# power.net
KiCad netlist of a schematic drawn in EAGLE
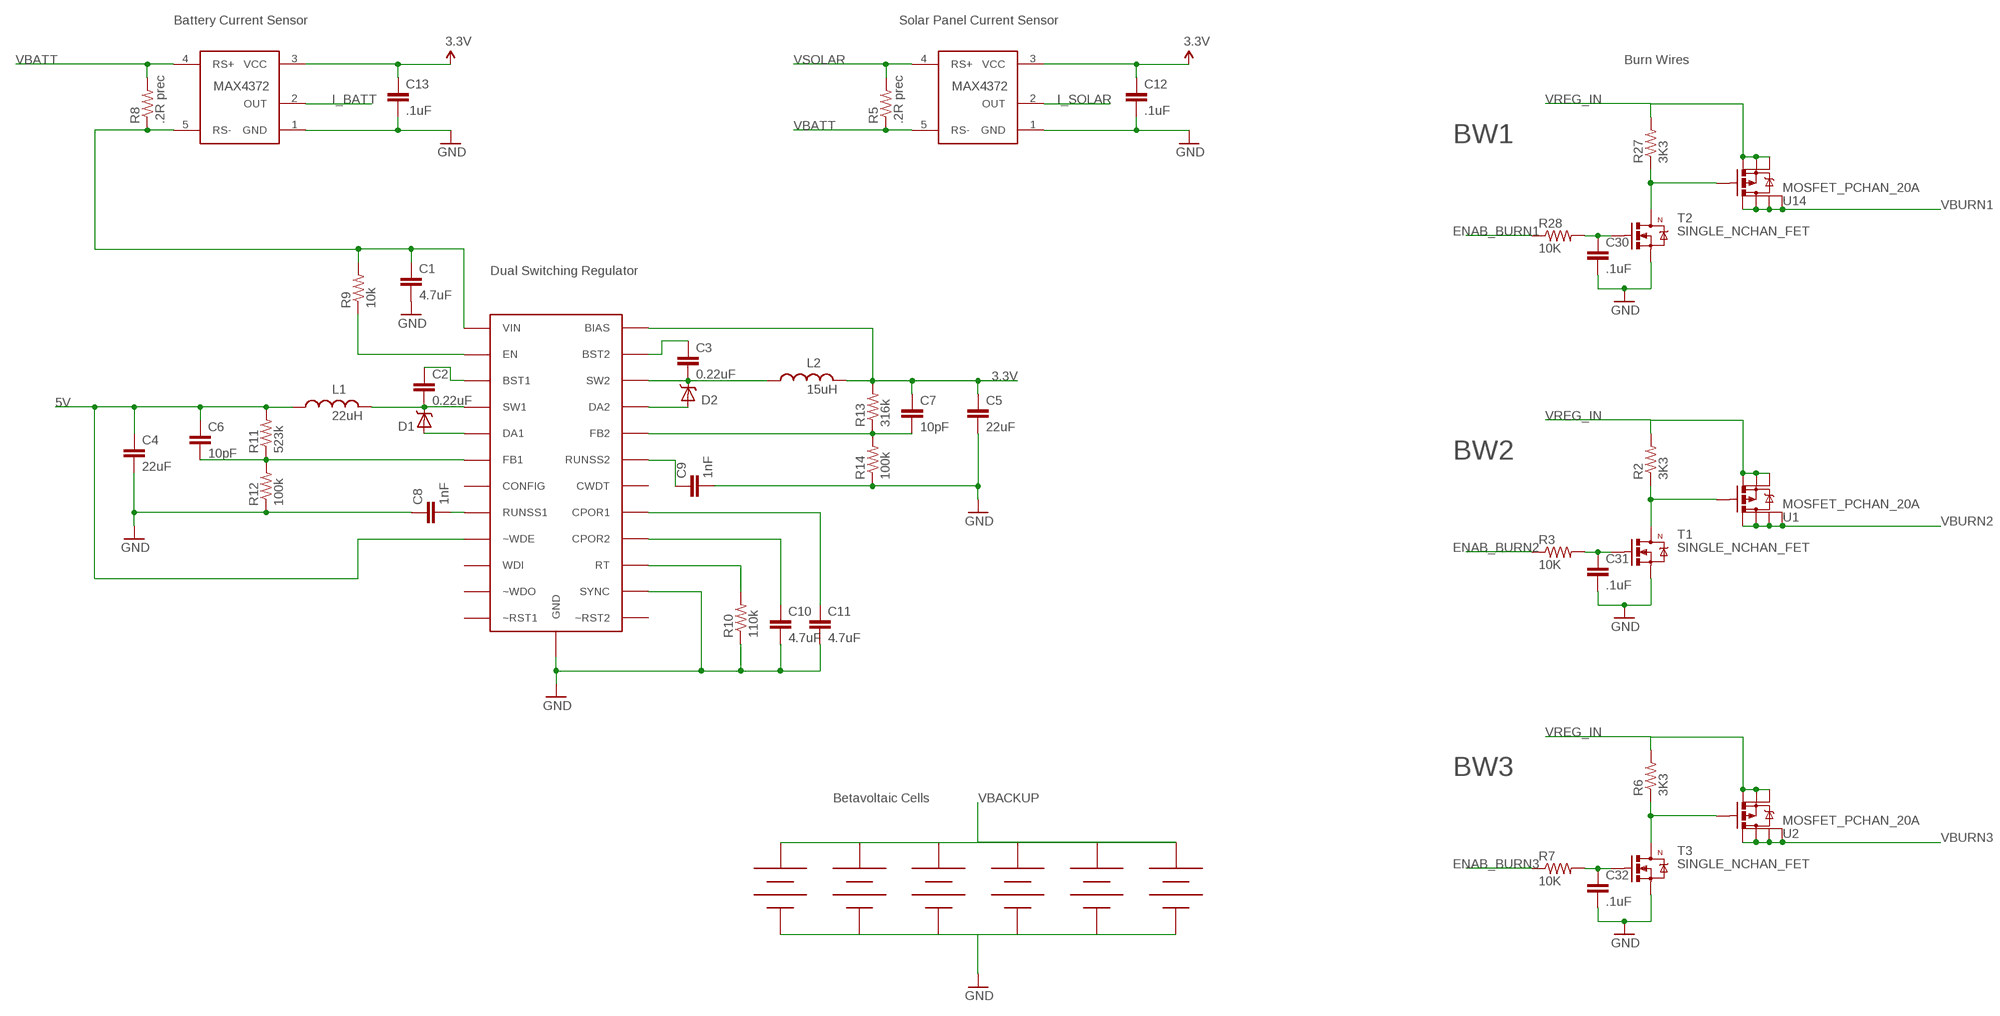
[diagram p0: schematic, sheet 1]
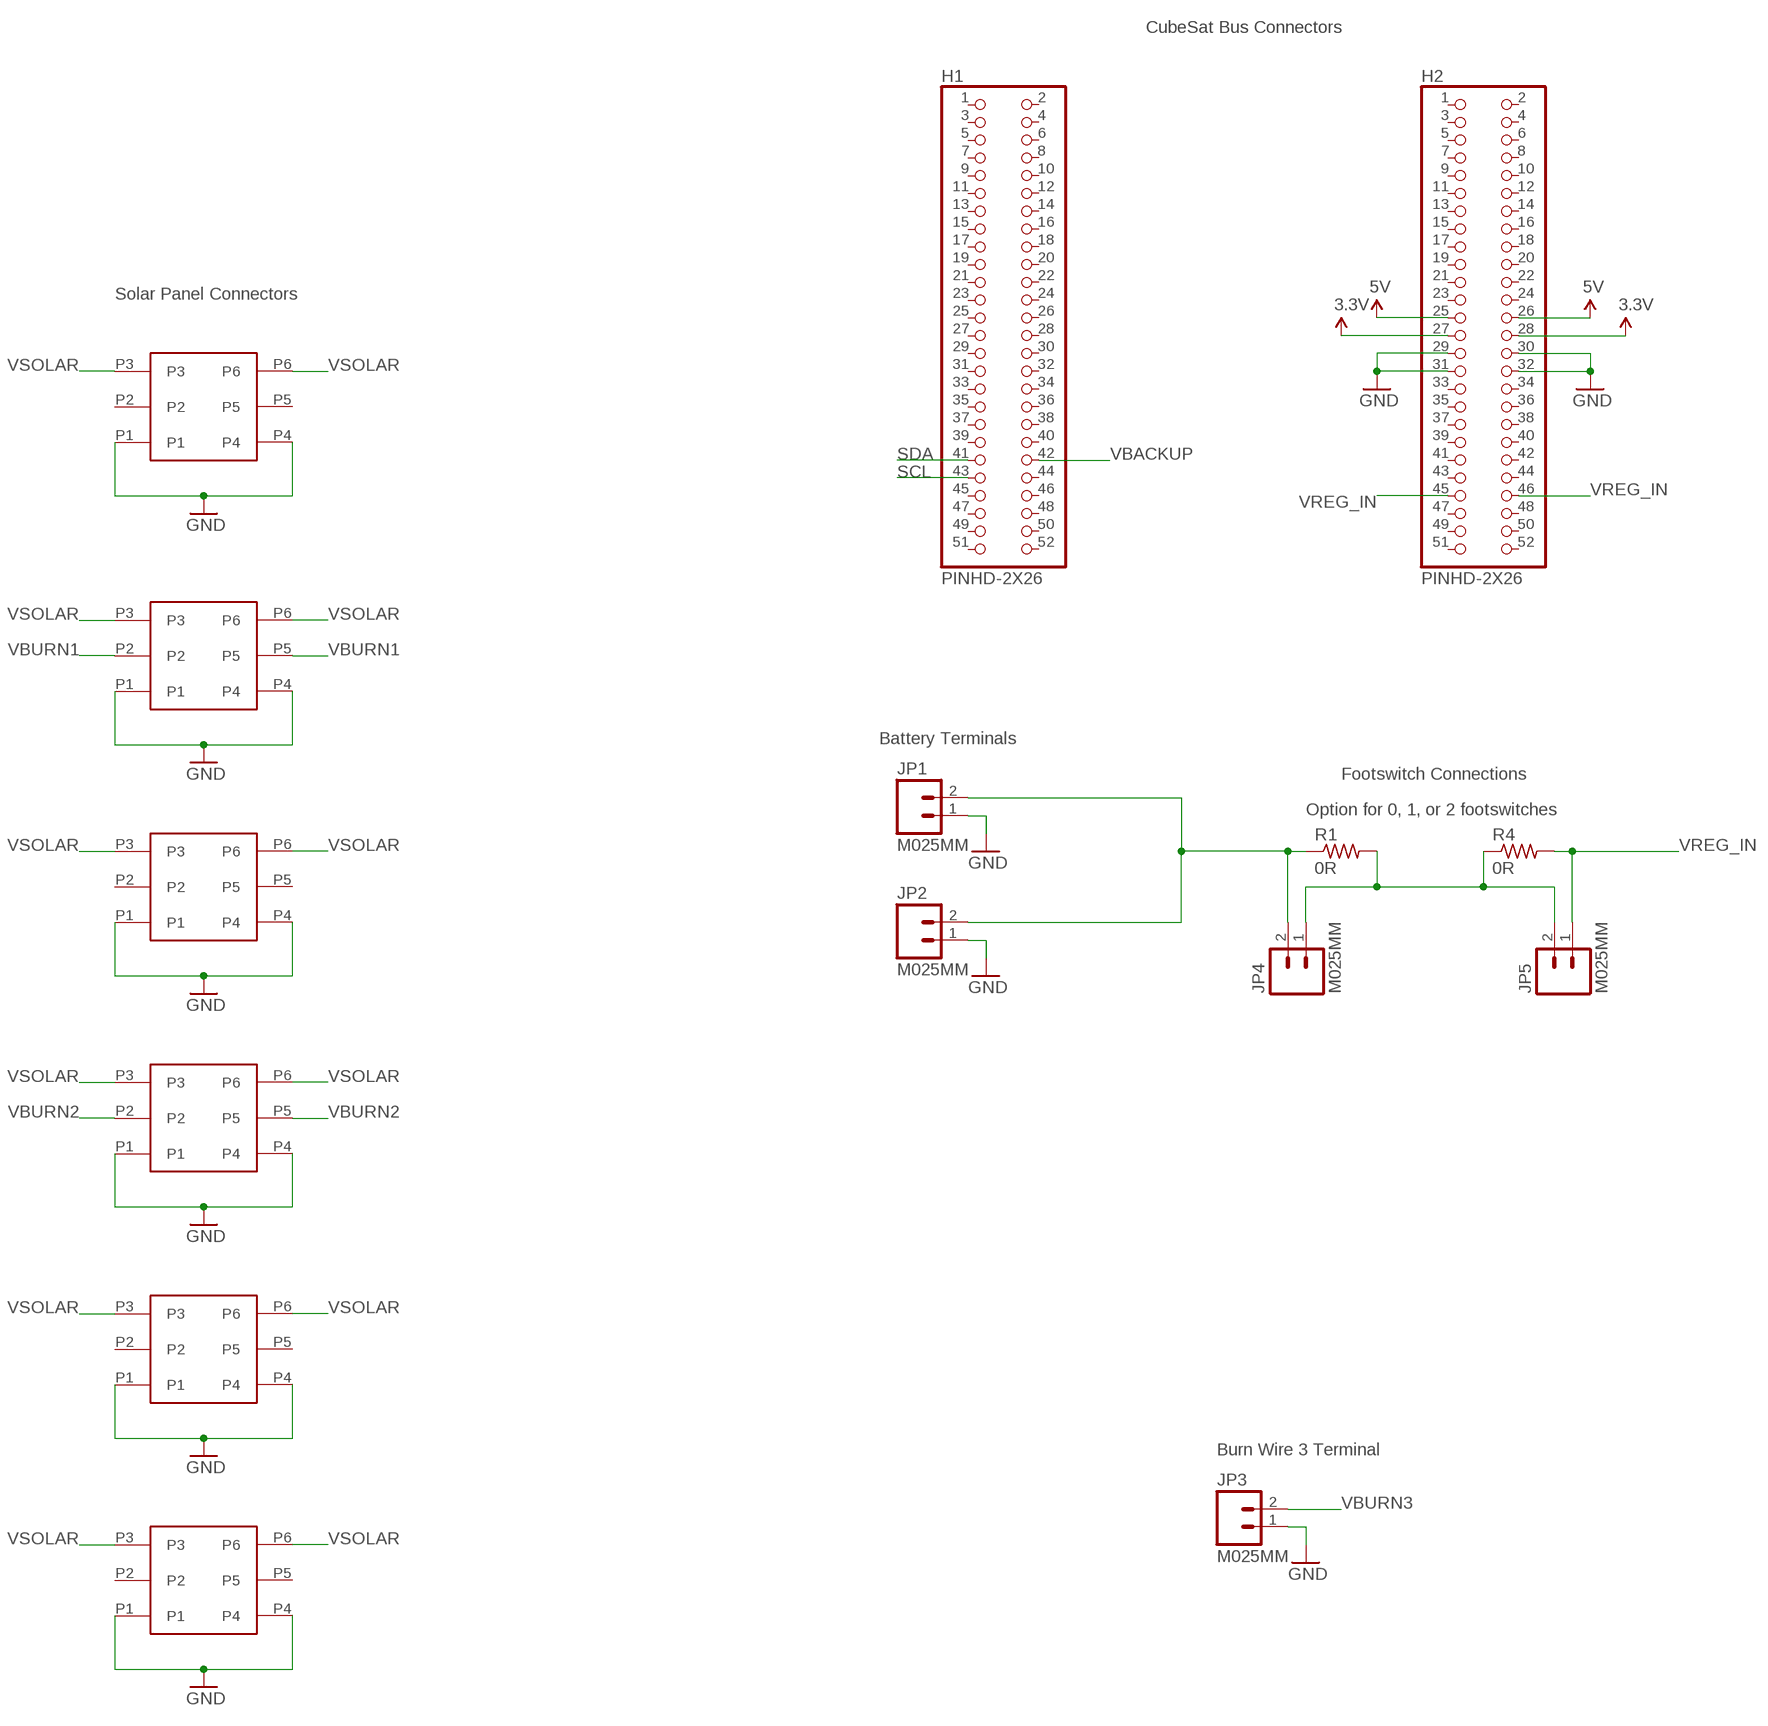
[diagram p1: schematic, sheet 2]

(export (version "E")
  (design (tool "Eeschema 10.0.6"))
  (components
    (comp (ref "H1")
      (value "PINHD-2X26")
      (footprint "eagle-import:2X26")
      (libsource (lib "eagle-import") (part "PINHD-2X26"))
    )
    (comp (ref "H2")
      (value "PINHD-2X26")
      (footprint "eagle-import:2X26")
      (libsource (lib "eagle-import") (part "PINHD-2X26"))
    )
    (comp (ref "JP1")
      (value "M025MM")
      (footprint "eagle-import:SCREWTERMINAL-5MM-2")
      (libsource (lib "eagle-import") (part "M025MM"))
    )
    (comp (ref "JP2")
      (value "M025MM")
      (footprint "eagle-import:SCREWTERMINAL-5MM-2")
      (libsource (lib "eagle-import") (part "M025MM"))
    )
    (comp (ref "JP3")
      (value "M025MM")
      (footprint "eagle-import:SCREWTERMINAL-5MM-2")
      (libsource (lib "eagle-import") (part "M025MM"))
    )
    (comp (ref "JP4")
      (value "M025MM")
      (footprint "eagle-import:SCREWTERMINAL-5MM-2")
      (libsource (lib "eagle-import") (part "M025MM"))
    )
    (comp (ref "JP5")
      (value "M025MM")
      (footprint "eagle-import:SCREWTERMINAL-5MM-2")
      (libsource (lib "eagle-import") (part "M025MM"))
    )
    (comp (ref "R1")
      (value "0R")
      (footprint "eagle-import:R1210")
      (libsource (lib "eagle-import") (part "R-US_R1210"))
    )
    (comp (ref "R4")
      (value "0R")
      (footprint "eagle-import:R1210")
      (libsource (lib "eagle-import") (part "R-US_R1210"))
    )
    (comp (ref "U$1")
      (value "G125-FV20605L0P")
      (footprint "eagle-import:G125-FV20605L0P")
      (libsource (lib "eagle-import") (part "G125-FV20605L0P"))
    )
    (comp (ref "U$2")
      (value "G125-FV20605L0P")
      (footprint "eagle-import:G125-FV20605L0P")
      (libsource (lib "eagle-import") (part "G125-FV20605L0P"))
    )
    (comp (ref "U$3")
      (value "G125-FV20605L0P")
      (footprint "eagle-import:G125-FV20605L0P")
      (libsource (lib "eagle-import") (part "G125-FV20605L0P"))
    )
    (comp (ref "U$4")
      (value "G125-FV20605L0P")
      (footprint "eagle-import:G125-FV20605L0P")
      (libsource (lib "eagle-import") (part "G125-FV20605L0P"))
    )
    (comp (ref "U$5")
      (value "G125-FV20605L0P")
      (footprint "eagle-import:G125-FV20605L0P")
      (libsource (lib "eagle-import") (part "G125-FV20605L0P"))
    )
    (comp (ref "U$6")
      (value "G125-FV20605L0P")
      (footprint "eagle-import:G125-FV20605L0P")
      (libsource (lib "eagle-import") (part "G125-FV20605L0P"))
    )
    (comp (ref "C1")
      (value "4.7uF")
      (footprint "eagle-import:0805")
      (libsource (lib "eagle-import") (part "CAP0805"))
    )
    (comp (ref "C2")
      (value "0.22uF")
      (footprint "eagle-import:0805")
      (libsource (lib "eagle-import") (part "CAP0805"))
    )
    (comp (ref "C3")
      (value "0.22uF")
      (footprint "eagle-import:0805")
      (libsource (lib "eagle-import") (part "CAP0805"))
    )
    (comp (ref "C4")
      (value "22uF")
      (footprint "eagle-import:1210")
      (libsource (lib "eagle-import") (part "CAP1210"))
    )
    (comp (ref "C5")
      (value "22uF")
      (footprint "eagle-import:1210")
      (libsource (lib "eagle-import") (part "CAP1210"))
    )
    (comp (ref "C6")
      (value "10pF")
      (footprint "eagle-import:0805")
      (libsource (lib "eagle-import") (part "CAP0805"))
    )
    (comp (ref "C7")
      (value "10pF")
      (footprint "eagle-import:0805")
      (libsource (lib "eagle-import") (part "CAP0805"))
    )
    (comp (ref "C8")
      (value "1nF")
      (footprint "eagle-import:0805")
      (libsource (lib "eagle-import") (part "CAP0805"))
    )
    (comp (ref "C9")
      (value "1nF")
      (footprint "eagle-import:0805")
      (libsource (lib "eagle-import") (part "CAP0805"))
    )
    (comp (ref "C10")
      (value "4.7uF")
      (footprint "eagle-import:0805")
      (libsource (lib "eagle-import") (part "CAP0805"))
    )
    (comp (ref "C11")
      (value "4.7uF")
      (footprint "eagle-import:0805")
      (libsource (lib "eagle-import") (part "CAP0805"))
    )
    (comp (ref "C12")
      (value ".1uF")
      (footprint "eagle-import:0805")
      (libsource (lib "eagle-import") (part "CAP0805"))
    )
    (comp (ref "C13")
      (value ".1uF")
      (footprint "eagle-import:0805")
      (libsource (lib "eagle-import") (part "CAP0805"))
    )
    (comp (ref "C30")
      (value ".1uF")
      (footprint "eagle-import:0805")
      (libsource (lib "eagle-import") (part "CAP0805"))
    )
    (comp (ref "C31")
      (value ".1uF")
      (footprint "eagle-import:0805")
      (libsource (lib "eagle-import") (part "CAP0805"))
    )
    (comp (ref "C32")
      (value ".1uF")
      (footprint "eagle-import:0805")
      (libsource (lib "eagle-import") (part "CAP0805"))
    )
    (comp (ref "D1")
      (value "BAT20J")
      (footprint "eagle-import:SOD-323")
      (libsource (lib "eagle-import") (part "DIODE-SCHOTTKY-BAT20J"))
    )
    (comp (ref "D2")
      (value "BAT20J")
      (footprint "eagle-import:SOD-323")
      (libsource (lib "eagle-import") (part "DIODE-SCHOTTKY-BAT20J"))
    )
    (comp (ref "L1")
      (value "SLF10145")
      (footprint "eagle-import:SLF10145")
      (libsource (lib "eagle-import") (part "SLF10145"))
    )
    (comp (ref "L2")
      (value "SLF10145")
      (footprint "eagle-import:SLF10145")
      (libsource (lib "eagle-import") (part "SLF10145"))
    )
    (comp (ref "R2")
      (value "3K3")
      (footprint "eagle-import:0805")
      (libsource (lib "eagle-import") (part "RESISTOR0805-RES"))
    )
    (comp (ref "R3")
      (value "10K")
      (footprint "eagle-import:0805")
      (libsource (lib "eagle-import") (part "RESISTOR0805-RES"))
    )
    (comp (ref "R5")
      (value ".2R prec")
      (footprint "eagle-import:0805")
      (libsource (lib "eagle-import") (part "RESISTOR0805-RES"))
    )
    (comp (ref "R6")
      (value "3K3")
      (footprint "eagle-import:0805")
      (libsource (lib "eagle-import") (part "RESISTOR0805-RES"))
    )
    (comp (ref "R7")
      (value "10K")
      (footprint "eagle-import:0805")
      (libsource (lib "eagle-import") (part "RESISTOR0805-RES"))
    )
    (comp (ref "R8")
      (value ".2R prec")
      (footprint "eagle-import:0805")
      (libsource (lib "eagle-import") (part "RESISTOR0805-RES"))
    )
    (comp (ref "R9")
      (value "10k")
      (footprint "eagle-import:0805")
      (libsource (lib "eagle-import") (part "RESISTOR0805-RES"))
    )
    (comp (ref "R10")
      (value "110k")
      (footprint "eagle-import:0805")
      (libsource (lib "eagle-import") (part "RESISTOR0805-RES"))
    )
    (comp (ref "R11")
      (value "523k")
      (footprint "eagle-import:0805")
      (libsource (lib "eagle-import") (part "RESISTOR0805-RES"))
    )
    (comp (ref "R12")
      (value "100k")
      (footprint "eagle-import:0805")
      (libsource (lib "eagle-import") (part "RESISTOR0805-RES"))
    )
    (comp (ref "R13")
      (value "316k")
      (footprint "eagle-import:0805")
      (libsource (lib "eagle-import") (part "RESISTOR0805-RES"))
    )
    (comp (ref "R14")
      (value "100k")
      (footprint "eagle-import:0805")
      (libsource (lib "eagle-import") (part "RESISTOR0805-RES"))
    )
    (comp (ref "R27")
      (value "3K3")
      (footprint "eagle-import:0805")
      (libsource (lib "eagle-import") (part "RESISTOR0805-RES"))
    )
    (comp (ref "R28")
      (value "10K")
      (footprint "eagle-import:0805")
      (libsource (lib "eagle-import") (part "RESISTOR0805-RES"))
    )
    (comp (ref "T1")
      (value "SINGLE_NCHAN_FET")
      (footprint "eagle-import:SOT23-3")
      (libsource (lib "eagle-import") (part "SINGLE_NCHAN_FET"))
    )
    (comp (ref "T2")
      (value "SINGLE_NCHAN_FET")
      (footprint "eagle-import:SOT23-3")
      (libsource (lib "eagle-import") (part "SINGLE_NCHAN_FET"))
    )
    (comp (ref "T3")
      (value "SINGLE_NCHAN_FET")
      (footprint "eagle-import:SOT23-3")
      (libsource (lib "eagle-import") (part "SINGLE_NCHAN_FET"))
    )
    (comp (ref "U$7")
      (value "BETABATTERY")
      (footprint "eagle-import:BETABATTERY")
      (libsource (lib "eagle-import") (part "BETABATTERY"))
    )
    (comp (ref "U$8")
      (value "BETABATTERY")
      (footprint "eagle-import:BETABATTERY")
      (libsource (lib "eagle-import") (part "BETABATTERY"))
    )
    (comp (ref "U$9")
      (value "BETABATTERY")
      (footprint "eagle-import:BETABATTERY")
      (libsource (lib "eagle-import") (part "BETABATTERY"))
    )
    (comp (ref "U$10")
      (value "BETABATTERY")
      (footprint "eagle-import:BETABATTERY")
      (libsource (lib "eagle-import") (part "BETABATTERY"))
    )
    (comp (ref "U$11")
      (value "BETABATTERY")
      (footprint "eagle-import:BETABATTERY")
      (libsource (lib "eagle-import") (part "BETABATTERY"))
    )
    (comp (ref "U$12")
      (value "BETABATTERY")
      (footprint "eagle-import:BETABATTERY")
      (libsource (lib "eagle-import") (part "BETABATTERY"))
    )
    (comp (ref "U$13")
      (value "LT3688")
      (footprint "eagle-import:LT3688TSSOP")
      (libsource (lib "eagle-import") (part "LT3688"))
    )
    (comp (ref "U$14")
      (value "CURRENT_MAX4372")
      (footprint "eagle-import:SOT23-5")
      (libsource (lib "eagle-import") (part "CURRENT_MAX4372"))
    )
    (comp (ref "U$15")
      (value "CURRENT_MAX4372")
      (footprint "eagle-import:SOT23-5")
      (libsource (lib "eagle-import") (part "CURRENT_MAX4372"))
    )
    (comp (ref "U1")
      (value "MOSFET_PCHAN_20A")
      (footprint "eagle-import:SO8")
      (libsource (lib "eagle-import") (part "MOSFET_PCHAN_20A"))
    )
    (comp (ref "U2")
      (value "MOSFET_PCHAN_20A")
      (footprint "eagle-import:SO8")
      (libsource (lib "eagle-import") (part "MOSFET_PCHAN_20A"))
    )
    (comp (ref "U14")
      (value "MOSFET_PCHAN_20A")
      (footprint "eagle-import:SO8")
      (libsource (lib "eagle-import") (part "MOSFET_PCHAN_20A"))
    )
  )
  (nets
    (net (code "1") (name "3.3V") (class "Default")
      (node (ref "C12") (pin "1") (pinfunction "1_1") (pintype "passive"))
      (node (ref "C13") (pin "1") (pinfunction "1_1") (pintype "passive"))
      (node (ref "C5") (pin "1") (pinfunction "1_1") (pintype "passive"))
      (node (ref "C7") (pin "1") (pinfunction "1_1") (pintype "passive"))
      (node (ref "H2") (pin "27") (pinfunction "27_27") (pintype "passive"))
      (node (ref "H2") (pin "28") (pinfunction "28_28") (pintype "passive"))
      (node (ref "L2") (pin "P2") (pinfunction "P2_P2") (pintype "bidirectional"))
      (node (ref "R13") (pin "2") (pinfunction "2_2") (pintype "passive"))
      (node (ref "U$13") (pin "BIAS") (pinfunction "BIAS_BIAS") (pintype "bidirectional"))
      (node (ref "U$14") (pin "3") (pinfunction "VCC_3") (pintype "bidirectional"))
      (node (ref "U$15") (pin "3") (pinfunction "VCC_3") (pintype "bidirectional"))
    )
    (net (code "2") (name "5V") (class "Default")
      (node (ref "C4") (pin "1") (pinfunction "1_1") (pintype "passive"))
      (node (ref "C6") (pin "1") (pinfunction "1_1") (pintype "passive"))
      (node (ref "H2") (pin "25") (pinfunction "25_25") (pintype "passive"))
      (node (ref "H2") (pin "26") (pinfunction "26_26") (pintype "passive"))
      (node (ref "L1") (pin "P1") (pinfunction "P1_P1") (pintype "bidirectional"))
      (node (ref "R11") (pin "2") (pinfunction "2_2") (pintype "passive"))
      (node (ref "U$13") (pin "WDE") (pinfunction "~{WDE}_WDE") (pintype "bidirectional"))
    )
    (net (code "3") (name "ENAB_BURN1") (class "Default")
      (node (ref "R28") (pin "1") (pinfunction "1_1") (pintype "passive"))
    )
    (net (code "4") (name "ENAB_BURN2") (class "Default")
      (node (ref "R3") (pin "1") (pinfunction "1_1") (pintype "passive"))
    )
    (net (code "5") (name "ENAB_BURN3") (class "Default")
      (node (ref "R7") (pin "1") (pinfunction "1_1") (pintype "passive"))
    )
    (net (code "6") (name "GND") (class "Default")
      (node (ref "C1") (pin "2") (pinfunction "2_2") (pintype "passive"))
      (node (ref "C10") (pin "2") (pinfunction "2_2") (pintype "passive"))
      (node (ref "C11") (pin "2") (pinfunction "2_2") (pintype "passive"))
      (node (ref "C12") (pin "2") (pinfunction "2_2") (pintype "passive"))
      (node (ref "C13") (pin "2") (pinfunction "2_2") (pintype "passive"))
      (node (ref "C30") (pin "2") (pinfunction "2_2") (pintype "passive"))
      (node (ref "C31") (pin "2") (pinfunction "2_2") (pintype "passive"))
      (node (ref "C32") (pin "2") (pinfunction "2_2") (pintype "passive"))
      (node (ref "C4") (pin "2") (pinfunction "2_2") (pintype "passive"))
      (node (ref "C5") (pin "2") (pinfunction "2_2") (pintype "passive"))
      (node (ref "C8") (pin "1") (pinfunction "1_1") (pintype "passive"))
      (node (ref "C9") (pin "2") (pinfunction "2_2") (pintype "passive"))
      (node (ref "H2") (pin "29") (pinfunction "29_29") (pintype "passive"))
      (node (ref "H2") (pin "30") (pinfunction "30_30") (pintype "passive"))
      (node (ref "H2") (pin "31") (pinfunction "31_31") (pintype "passive"))
      (node (ref "H2") (pin "32") (pinfunction "32_32") (pintype "passive"))
      (node (ref "JP1") (pin "1") (pinfunction "1_1") (pintype "passive"))
      (node (ref "JP2") (pin "1") (pinfunction "1_1") (pintype "passive"))
      (node (ref "JP3") (pin "1") (pinfunction "1_1") (pintype "passive"))
      (node (ref "R10") (pin "1") (pinfunction "1_1") (pintype "passive"))
      (node (ref "R12") (pin "1") (pinfunction "1_1") (pintype "passive"))
      (node (ref "R14") (pin "1") (pinfunction "1_1") (pintype "passive"))
      (node (ref "T1") (pin "2") (pinfunction "S_2") (pintype "passive"))
      (node (ref "T2") (pin "2") (pinfunction "S_2") (pintype "passive"))
      (node (ref "T3") (pin "2") (pinfunction "S_2") (pintype "passive"))
      (node (ref "U$1") (pin "P1") (pinfunction "P1_P1") (pintype "bidirectional"))
      (node (ref "U$1") (pin "P4") (pinfunction "P4_P4") (pintype "bidirectional"))
      (node (ref "U$10") (pin "V-") (pinfunction "V-_V-") (pintype "power_in"))
      (node (ref "U$11") (pin "V-") (pinfunction "V-_V-") (pintype "power_in"))
      (node (ref "U$12") (pin "V-") (pinfunction "V-_V-") (pintype "power_in"))
      (node (ref "U$13") (pin "GND") (pinfunction "GND_GND") (pintype "bidirectional"))
      (node (ref "U$13") (pin "SYNC") (pinfunction "SYNC_SYNC") (pintype "bidirectional"))
      (node (ref "U$14") (pin "1") (pinfunction "GND_1") (pintype "bidirectional"))
      (node (ref "U$15") (pin "1") (pinfunction "GND_1") (pintype "bidirectional"))
      (node (ref "U$2") (pin "P1") (pinfunction "P1_P1") (pintype "bidirectional"))
      (node (ref "U$2") (pin "P4") (pinfunction "P4_P4") (pintype "bidirectional"))
      (node (ref "U$3") (pin "P1") (pinfunction "P1_P1") (pintype "bidirectional"))
      (node (ref "U$3") (pin "P4") (pinfunction "P4_P4") (pintype "bidirectional"))
      (node (ref "U$4") (pin "P1") (pinfunction "P1_P1") (pintype "bidirectional"))
      (node (ref "U$4") (pin "P4") (pinfunction "P4_P4") (pintype "bidirectional"))
      (node (ref "U$5") (pin "P1") (pinfunction "P1_P1") (pintype "bidirectional"))
      (node (ref "U$5") (pin "P4") (pinfunction "P4_P4") (pintype "bidirectional"))
      (node (ref "U$6") (pin "P1") (pinfunction "P1_P1") (pintype "bidirectional"))
      (node (ref "U$6") (pin "P4") (pinfunction "P4_P4") (pintype "bidirectional"))
      (node (ref "U$7") (pin "V-") (pinfunction "V-_V-") (pintype "power_in"))
      (node (ref "U$8") (pin "V-") (pinfunction "V-_V-") (pintype "power_in"))
      (node (ref "U$9") (pin "V-") (pinfunction "V-_V-") (pintype "power_in"))
    )
    (net (code "7") (name "I_BATT") (class "Default")
      (node (ref "U$15") (pin "2") (pinfunction "OUT_2") (pintype "bidirectional"))
    )
    (net (code "8") (name "I_SOLAR") (class "Default")
      (node (ref "U$14") (pin "2") (pinfunction "OUT_2") (pintype "bidirectional"))
    )
    (net (code "9") (name "Net-(C2-Pad1)") (class "Default")
      (node (ref "C2") (pin "1") (pinfunction "1_1") (pintype "passive"))
      (node (ref "U$13") (pin "BST1") (pinfunction "BST1_BST1") (pintype "bidirectional"))
    )
    (net (code "10") (name "Net-(C2-Pad2)") (class "Default")
      (node (ref "C2") (pin "2") (pinfunction "2_2") (pintype "passive"))
      (node (ref "D1") (pin "C") (pinfunction "C_C") (pintype "passive"))
      (node (ref "L1") (pin "P2") (pinfunction "P2_P2") (pintype "bidirectional"))
      (node (ref "U$13") (pin "SW1") (pinfunction "SW1_SW1") (pintype "bidirectional"))
    )
    (net (code "11") (name "Net-(C3-Pad1)") (class "Default")
      (node (ref "C3") (pin "1") (pinfunction "1_1") (pintype "passive"))
      (node (ref "U$13") (pin "BST2") (pinfunction "BST2_BST2") (pintype "bidirectional"))
    )
    (net (code "12") (name "Net-(C3-Pad2)") (class "Default")
      (node (ref "C3") (pin "2") (pinfunction "2_2") (pintype "passive"))
      (node (ref "D2") (pin "C") (pinfunction "C_C") (pintype "passive"))
      (node (ref "L2") (pin "P1") (pinfunction "P1_P1") (pintype "bidirectional"))
      (node (ref "U$13") (pin "SW2") (pinfunction "SW2_SW2") (pintype "bidirectional"))
    )
    (net (code "13") (name "Net-(C6-Pad2)") (class "Default")
      (node (ref "C6") (pin "2") (pinfunction "2_2") (pintype "passive"))
      (node (ref "R11") (pin "1") (pinfunction "1_1") (pintype "passive"))
      (node (ref "R12") (pin "2") (pinfunction "2_2") (pintype "passive"))
      (node (ref "U$13") (pin "FB1") (pinfunction "FB1_FB1") (pintype "bidirectional"))
    )
    (net (code "14") (name "Net-(C7-Pad2)") (class "Default")
      (node (ref "C7") (pin "2") (pinfunction "2_2") (pintype "passive"))
      (node (ref "R13") (pin "1") (pinfunction "1_1") (pintype "passive"))
      (node (ref "R14") (pin "2") (pinfunction "2_2") (pintype "passive"))
      (node (ref "U$13") (pin "FB2") (pinfunction "FB2_FB2") (pintype "bidirectional"))
    )
    (net (code "15") (name "Net-(C8-Pad2)") (class "Default")
      (node (ref "C8") (pin "2") (pinfunction "2_2") (pintype "passive"))
      (node (ref "U$13") (pin "RUNSS1") (pinfunction "RUNSS1_RUNSS1") (pintype "bidirectional"))
    )
    (net (code "16") (name "Net-(C9-Pad1)") (class "Default")
      (node (ref "C9") (pin "1") (pinfunction "1_1") (pintype "passive"))
      (node (ref "U$13") (pin "RUNSS2") (pinfunction "RUNSS2_RUNSS2") (pintype "bidirectional"))
    )
    (net (code "17") (name "Net-(C10-Pad1)") (class "Default")
      (node (ref "C10") (pin "1") (pinfunction "1_1") (pintype "passive"))
      (node (ref "U$13") (pin "CPOR2") (pinfunction "CPOR2_CPOR2") (pintype "bidirectional"))
    )
    (net (code "18") (name "Net-(C11-Pad1)") (class "Default")
      (node (ref "C11") (pin "1") (pinfunction "1_1") (pintype "passive"))
      (node (ref "U$13") (pin "CPOR1") (pinfunction "CPOR1_CPOR1") (pintype "bidirectional"))
    )
    (net (code "19") (name "Net-(D1-PadA)") (class "Default")
      (node (ref "D1") (pin "A") (pinfunction "A_A") (pintype "passive"))
      (node (ref "U$13") (pin "DA1") (pinfunction "DA1_DA1") (pintype "bidirectional"))
    )
    (net (code "20") (name "Net-(D2-PadA)") (class "Default")
      (node (ref "D2") (pin "A") (pinfunction "A_A") (pintype "passive"))
      (node (ref "U$13") (pin "DA2") (pinfunction "DA2_DA2") (pintype "bidirectional"))
    )
    (net (code "21") (name "Net-(JP1-Pad2)") (class "Default")
      (node (ref "JP1") (pin "2") (pinfunction "2_2") (pintype "passive"))
      (node (ref "JP2") (pin "2") (pinfunction "2_2") (pintype "passive"))
      (node (ref "JP4") (pin "2") (pinfunction "2_2") (pintype "passive"))
      (node (ref "R1") (pin "1") (pinfunction "1_1") (pintype "passive"))
    )
    (net (code "22") (name "Net-(JP4-Pad1)") (class "Default")
      (node (ref "JP4") (pin "1") (pinfunction "1_1") (pintype "passive"))
      (node (ref "JP5") (pin "2") (pinfunction "2_2") (pintype "passive"))
      (node (ref "R1") (pin "2") (pinfunction "2_2") (pintype "passive"))
      (node (ref "R4") (pin "1") (pinfunction "1_1") (pintype "passive"))
    )
    (net (code "23") (name "Net-(R9-Pad1)") (class "Default")
      (node (ref "R9") (pin "1") (pinfunction "1_1") (pintype "passive"))
      (node (ref "U$13") (pin "EN") (pinfunction "EN_EN") (pintype "bidirectional"))
    )
    (net (code "24") (name "Net-(R10-Pad2)") (class "Default")
      (node (ref "R10") (pin "2") (pinfunction "2_2") (pintype "passive"))
      (node (ref "U$13") (pin "RT") (pinfunction "RT_RT") (pintype "bidirectional"))
    )
    (net (code "25") (name "Net-(T1-D)") (class "Default")
      (node (ref "R2") (pin "1") (pinfunction "1_1") (pintype "passive"))
      (node (ref "T1") (pin "3") (pinfunction "D_3") (pintype "passive"))
      (node (ref "U1") (pin "4") (pinfunction "G_4") (pintype "passive"))
    )
    (net (code "26") (name "Net-(T1-G)") (class "Default")
      (node (ref "C31") (pin "1") (pinfunction "1_1") (pintype "passive"))
      (node (ref "R3") (pin "2") (pinfunction "2_2") (pintype "passive"))
      (node (ref "T1") (pin "1") (pinfunction "G_1") (pintype "passive"))
    )
    (net (code "27") (name "Net-(T2-D)") (class "Default")
      (node (ref "R27") (pin "1") (pinfunction "1_1") (pintype "passive"))
      (node (ref "T2") (pin "3") (pinfunction "D_3") (pintype "passive"))
      (node (ref "U14") (pin "4") (pinfunction "G_4") (pintype "passive"))
    )
    (net (code "28") (name "Net-(T2-G)") (class "Default")
      (node (ref "C30") (pin "1") (pinfunction "1_1") (pintype "passive"))
      (node (ref "R28") (pin "2") (pinfunction "2_2") (pintype "passive"))
      (node (ref "T2") (pin "1") (pinfunction "G_1") (pintype "passive"))
    )
    (net (code "29") (name "Net-(T3-D)") (class "Default")
      (node (ref "R6") (pin "1") (pinfunction "1_1") (pintype "passive"))
      (node (ref "T3") (pin "3") (pinfunction "D_3") (pintype "passive"))
      (node (ref "U2") (pin "4") (pinfunction "G_4") (pintype "passive"))
    )
    (net (code "30") (name "Net-(T3-G)") (class "Default")
      (node (ref "C32") (pin "1") (pinfunction "1_1") (pintype "passive"))
      (node (ref "R7") (pin "2") (pinfunction "2_2") (pintype "passive"))
      (node (ref "T3") (pin "1") (pinfunction "G_1") (pintype "passive"))
    )
    (net (code "31") (name "SCL") (class "Default")
      (node (ref "H1") (pin "43") (pinfunction "43_43") (pintype "passive"))
    )
    (net (code "32") (name "SDA") (class "Default")
      (node (ref "H1") (pin "41") (pinfunction "41_41") (pintype "passive"))
    )
    (net (code "33") (name "VBACKUP") (class "Default")
      (node (ref "H1") (pin "42") (pinfunction "42_42") (pintype "passive"))
      (node (ref "U$10") (pin "V+") (pinfunction "V+_V+") (pintype "power_in"))
      (node (ref "U$11") (pin "V+") (pinfunction "V+_V+") (pintype "power_in"))
      (node (ref "U$12") (pin "V+") (pinfunction "V+_V+") (pintype "power_in"))
      (node (ref "U$7") (pin "V+") (pinfunction "V+_V+") (pintype "power_in"))
      (node (ref "U$8") (pin "V+") (pinfunction "V+_V+") (pintype "power_in"))
      (node (ref "U$9") (pin "V+") (pinfunction "V+_V+") (pintype "power_in"))
    )
    (net (code "34") (name "VBATT") (class "Default")
      (node (ref "R5") (pin "1") (pinfunction "1_1") (pintype "passive"))
      (node (ref "R8") (pin "2") (pinfunction "2_2") (pintype "passive"))
      (node (ref "U$14") (pin "5") (pinfunction "RS-_5") (pintype "bidirectional"))
      (node (ref "U$15") (pin "4") (pinfunction "RS+_4") (pintype "bidirectional"))
    )
    (net (code "35") (name "VBURN1") (class "Default")
      (node (ref "U$6") (pin "P2") (pinfunction "P2_P2") (pintype "bidirectional"))
      (node (ref "U$6") (pin "P5") (pinfunction "P5_P5") (pintype "bidirectional"))
      (node (ref "U14") (pin "5") (pinfunction "D_5") (pintype "passive"))
      (node (ref "U14") (pin "6") (pinfunction "D_6") (pintype "passive"))
      (node (ref "U14") (pin "7") (pinfunction "D_7") (pintype "passive"))
      (node (ref "U14") (pin "8") (pinfunction "D_8") (pintype "passive"))
    )
    (net (code "36") (name "VBURN2") (class "Default")
      (node (ref "U$1") (pin "P2") (pinfunction "P2_P2") (pintype "bidirectional"))
      (node (ref "U$1") (pin "P5") (pinfunction "P5_P5") (pintype "bidirectional"))
      (node (ref "U1") (pin "5") (pinfunction "D_5") (pintype "passive"))
      (node (ref "U1") (pin "6") (pinfunction "D_6") (pintype "passive"))
      (node (ref "U1") (pin "7") (pinfunction "D_7") (pintype "passive"))
      (node (ref "U1") (pin "8") (pinfunction "D_8") (pintype "passive"))
    )
    (net (code "37") (name "VBURN3") (class "Default")
      (node (ref "JP3") (pin "2") (pinfunction "2_2") (pintype "passive"))
      (node (ref "U2") (pin "5") (pinfunction "D_5") (pintype "passive"))
      (node (ref "U2") (pin "6") (pinfunction "D_6") (pintype "passive"))
      (node (ref "U2") (pin "7") (pinfunction "D_7") (pintype "passive"))
      (node (ref "U2") (pin "8") (pinfunction "D_8") (pintype "passive"))
    )
    (net (code "38") (name "VREG_IN") (class "Default")
      (node (ref "C1") (pin "1") (pinfunction "1_1") (pintype "passive"))
      (node (ref "H2") (pin "45") (pinfunction "45_45") (pintype "passive"))
      (node (ref "H2") (pin "46") (pinfunction "46_46") (pintype "passive"))
      (node (ref "JP5") (pin "1") (pinfunction "1_1") (pintype "passive"))
      (node (ref "R2") (pin "2") (pinfunction "2_2") (pintype "passive"))
      (node (ref "R27") (pin "2") (pinfunction "2_2") (pintype "passive"))
      (node (ref "R4") (pin "2") (pinfunction "2_2") (pintype "passive"))
      (node (ref "R6") (pin "2") (pinfunction "2_2") (pintype "passive"))
      (node (ref "R8") (pin "1") (pinfunction "1_1") (pintype "passive"))
      (node (ref "R9") (pin "2") (pinfunction "2_2") (pintype "passive"))
      (node (ref "U$13") (pin "VIN") (pinfunction "VIN_VIN") (pintype "bidirectional"))
      (node (ref "U$15") (pin "5") (pinfunction "RS-_5") (pintype "bidirectional"))
      (node (ref "U1") (pin "1") (pinfunction "S_1") (pintype "passive"))
      (node (ref "U1") (pin "2") (pinfunction "S_2") (pintype "passive"))
      (node (ref "U1") (pin "3") (pinfunction "S_3") (pintype "passive"))
      (node (ref "U14") (pin "1") (pinfunction "S_1") (pintype "passive"))
      (node (ref "U14") (pin "2") (pinfunction "S_2") (pintype "passive"))
      (node (ref "U14") (pin "3") (pinfunction "S_3") (pintype "passive"))
      (node (ref "U2") (pin "1") (pinfunction "S_1") (pintype "passive"))
      (node (ref "U2") (pin "2") (pinfunction "S_2") (pintype "passive"))
      (node (ref "U2") (pin "3") (pinfunction "S_3") (pintype "passive"))
    )
    (net (code "39") (name "VSOLAR") (class "Default")
      (node (ref "R5") (pin "2") (pinfunction "2_2") (pintype "passive"))
      (node (ref "U$1") (pin "P3") (pinfunction "P3_P3") (pintype "bidirectional"))
      (node (ref "U$1") (pin "P6") (pinfunction "P6_P6") (pintype "bidirectional"))
      (node (ref "U$14") (pin "4") (pinfunction "RS+_4") (pintype "bidirectional"))
      (node (ref "U$2") (pin "P3") (pinfunction "P3_P3") (pintype "bidirectional"))
      (node (ref "U$2") (pin "P6") (pinfunction "P6_P6") (pintype "bidirectional"))
      (node (ref "U$3") (pin "P3") (pinfunction "P3_P3") (pintype "bidirectional"))
      (node (ref "U$3") (pin "P6") (pinfunction "P6_P6") (pintype "bidirectional"))
      (node (ref "U$4") (pin "P3") (pinfunction "P3_P3") (pintype "bidirectional"))
      (node (ref "U$4") (pin "P6") (pinfunction "P6_P6") (pintype "bidirectional"))
      (node (ref "U$5") (pin "P3") (pinfunction "P3_P3") (pintype "bidirectional"))
      (node (ref "U$5") (pin "P6") (pinfunction "P6_P6") (pintype "bidirectional"))
      (node (ref "U$6") (pin "P3") (pinfunction "P3_P3") (pintype "bidirectional"))
      (node (ref "U$6") (pin "P6") (pinfunction "P6_P6") (pintype "bidirectional"))
    )
    (net (code "40") (name "unconnected-(H1-Pad1)") (class "Default")
      (node (ref "H1") (pin "1") (pinfunction "1_1") (pintype "passive"))
    )
    (net (code "41") (name "unconnected-(H1-Pad2)") (class "Default")
      (node (ref "H1") (pin "2") (pinfunction "2_2") (pintype "passive"))
    )
    (net (code "42") (name "unconnected-(H1-Pad3)") (class "Default")
      (node (ref "H1") (pin "3") (pinfunction "3_3") (pintype "passive"))
    )
    (net (code "43") (name "unconnected-(H1-Pad4)") (class "Default")
      (node (ref "H1") (pin "4") (pinfunction "4_4") (pintype "passive"))
    )
    (net (code "44") (name "unconnected-(H1-Pad5)") (class "Default")
      (node (ref "H1") (pin "5") (pinfunction "5_5") (pintype "passive"))
    )
    (net (code "45") (name "unconnected-(H1-Pad6)") (class "Default")
      (node (ref "H1") (pin "6") (pinfunction "6_6") (pintype "passive"))
    )
    (net (code "46") (name "unconnected-(H1-Pad7)") (class "Default")
      (node (ref "H1") (pin "7") (pinfunction "7_7") (pintype "passive"))
    )
    (net (code "47") (name "unconnected-(H1-Pad8)") (class "Default")
      (node (ref "H1") (pin "8") (pinfunction "8_8") (pintype "passive"))
    )
    (net (code "48") (name "unconnected-(H1-Pad9)") (class "Default")
      (node (ref "H1") (pin "9") (pinfunction "9_9") (pintype "passive"))
    )
    (net (code "49") (name "unconnected-(H1-Pad10)") (class "Default")
      (node (ref "H1") (pin "10") (pinfunction "10_10") (pintype "passive"))
    )
    (net (code "50") (name "unconnected-(H1-Pad11)") (class "Default")
      (node (ref "H1") (pin "11") (pinfunction "11_11") (pintype "passive"))
    )
    (net (code "51") (name "unconnected-(H1-Pad12)") (class "Default")
      (node (ref "H1") (pin "12") (pinfunction "12_12") (pintype "passive"))
    )
    (net (code "52") (name "unconnected-(H1-Pad13)") (class "Default")
      (node (ref "H1") (pin "13") (pinfunction "13_13") (pintype "passive"))
    )
    (net (code "53") (name "unconnected-(H1-Pad14)") (class "Default")
      (node (ref "H1") (pin "14") (pinfunction "14_14") (pintype "passive"))
    )
    (net (code "54") (name "unconnected-(H1-Pad15)") (class "Default")
      (node (ref "H1") (pin "15") (pinfunction "15_15") (pintype "passive"))
    )
    (net (code "55") (name "unconnected-(H1-Pad16)") (class "Default")
      (node (ref "H1") (pin "16") (pinfunction "16_16") (pintype "passive"))
    )
    (net (code "56") (name "unconnected-(H1-Pad17)") (class "Default")
      (node (ref "H1") (pin "17") (pinfunction "17_17") (pintype "passive"))
    )
    (net (code "57") (name "unconnected-(H1-Pad18)") (class "Default")
      (node (ref "H1") (pin "18") (pinfunction "18_18") (pintype "passive"))
    )
    (net (code "58") (name "unconnected-(H1-Pad19)") (class "Default")
      (node (ref "H1") (pin "19") (pinfunction "19_19") (pintype "passive"))
    )
    (net (code "59") (name "unconnected-(H1-Pad20)") (class "Default")
      (node (ref "H1") (pin "20") (pinfunction "20_20") (pintype "passive"))
    )
    (net (code "60") (name "unconnected-(H1-Pad21)") (class "Default")
      (node (ref "H1") (pin "21") (pinfunction "21_21") (pintype "passive"))
    )
    (net (code "61") (name "unconnected-(H1-Pad22)") (class "Default")
      (node (ref "H1") (pin "22") (pinfunction "22_22") (pintype "passive"))
    )
    (net (code "62") (name "unconnected-(H1-Pad23)") (class "Default")
      (node (ref "H1") (pin "23") (pinfunction "23_23") (pintype "passive"))
    )
    (net (code "63") (name "unconnected-(H1-Pad24)") (class "Default")
      (node (ref "H1") (pin "24") (pinfunction "24_24") (pintype "passive"))
    )
    (net (code "64") (name "unconnected-(H1-Pad25)") (class "Default")
      (node (ref "H1") (pin "25") (pinfunction "25_25") (pintype "passive"))
    )
    (net (code "65") (name "unconnected-(H1-Pad26)") (class "Default")
      (node (ref "H1") (pin "26") (pinfunction "26_26") (pintype "passive"))
    )
    (net (code "66") (name "unconnected-(H1-Pad27)") (class "Default")
      (node (ref "H1") (pin "27") (pinfunction "27_27") (pintype "passive"))
    )
    (net (code "67") (name "unconnected-(H1-Pad28)") (class "Default")
      (node (ref "H1") (pin "28") (pinfunction "28_28") (pintype "passive"))
    )
    (net (code "68") (name "unconnected-(H1-Pad29)") (class "Default")
      (node (ref "H1") (pin "29") (pinfunction "29_29") (pintype "passive"))
    )
    (net (code "69") (name "unconnected-(H1-Pad30)") (class "Default")
      (node (ref "H1") (pin "30") (pinfunction "30_30") (pintype "passive"))
    )
    (net (code "70") (name "unconnected-(H1-Pad31)") (class "Default")
      (node (ref "H1") (pin "31") (pinfunction "31_31") (pintype "passive"))
    )
    (net (code "71") (name "unconnected-(H1-Pad32)") (class "Default")
      (node (ref "H1") (pin "32") (pinfunction "32_32") (pintype "passive"))
    )
    (net (code "72") (name "unconnected-(H1-Pad33)") (class "Default")
      (node (ref "H1") (pin "33") (pinfunction "33_33") (pintype "passive"))
    )
    (net (code "73") (name "unconnected-(H1-Pad34)") (class "Default")
      (node (ref "H1") (pin "34") (pinfunction "34_34") (pintype "passive"))
    )
    (net (code "74") (name "unconnected-(H1-Pad35)") (class "Default")
      (node (ref "H1") (pin "35") (pinfunction "35_35") (pintype "passive"))
    )
    (net (code "75") (name "unconnected-(H1-Pad36)") (class "Default")
      (node (ref "H1") (pin "36") (pinfunction "36_36") (pintype "passive"))
    )
    (net (code "76") (name "unconnected-(H1-Pad37)") (class "Default")
      (node (ref "H1") (pin "37") (pinfunction "37_37") (pintype "passive"))
    )
    (net (code "77") (name "unconnected-(H1-Pad38)") (class "Default")
      (node (ref "H1") (pin "38") (pinfunction "38_38") (pintype "passive"))
    )
    (net (code "78") (name "unconnected-(H1-Pad39)") (class "Default")
      (node (ref "H1") (pin "39") (pinfunction "39_39") (pintype "passive"))
    )
    (net (code "79") (name "unconnected-(H1-Pad40)") (class "Default")
      (node (ref "H1") (pin "40") (pinfunction "40_40") (pintype "passive"))
    )
    (net (code "80") (name "unconnected-(H1-Pad44)") (class "Default")
      (node (ref "H1") (pin "44") (pinfunction "44_44") (pintype "passive"))
    )
    (net (code "81") (name "unconnected-(H1-Pad45)") (class "Default")
      (node (ref "H1") (pin "45") (pinfunction "45_45") (pintype "passive"))
    )
    (net (code "82") (name "unconnected-(H1-Pad46)") (class "Default")
      (node (ref "H1") (pin "46") (pinfunction "46_46") (pintype "passive"))
    )
    (net (code "83") (name "unconnected-(H1-Pad47)") (class "Default")
      (node (ref "H1") (pin "47") (pinfunction "47_47") (pintype "passive"))
    )
    (net (code "84") (name "unconnected-(H1-Pad48)") (class "Default")
      (node (ref "H1") (pin "48") (pinfunction "48_48") (pintype "passive"))
    )
    (net (code "85") (name "unconnected-(H1-Pad49)") (class "Default")
      (node (ref "H1") (pin "49") (pinfunction "49_49") (pintype "passive"))
    )
    (net (code "86") (name "unconnected-(H1-Pad50)") (class "Default")
      (node (ref "H1") (pin "50") (pinfunction "50_50") (pintype "passive"))
    )
    (net (code "87") (name "unconnected-(H1-Pad51)") (class "Default")
      (node (ref "H1") (pin "51") (pinfunction "51_51") (pintype "passive"))
    )
    (net (code "88") (name "unconnected-(H1-Pad52)") (class "Default")
      (node (ref "H1") (pin "52") (pinfunction "52_52") (pintype "passive"))
    )
    (net (code "89") (name "unconnected-(H2-Pad1)") (class "Default")
      (node (ref "H2") (pin "1") (pinfunction "1_1") (pintype "passive"))
    )
    (net (code "90") (name "unconnected-(H2-Pad2)") (class "Default")
      (node (ref "H2") (pin "2") (pinfunction "2_2") (pintype "passive"))
    )
    (net (code "91") (name "unconnected-(H2-Pad3)") (class "Default")
      (node (ref "H2") (pin "3") (pinfunction "3_3") (pintype "passive"))
    )
    (net (code "92") (name "unconnected-(H2-Pad4)") (class "Default")
      (node (ref "H2") (pin "4") (pinfunction "4_4") (pintype "passive"))
    )
    (net (code "93") (name "unconnected-(H2-Pad5)") (class "Default")
      (node (ref "H2") (pin "5") (pinfunction "5_5") (pintype "passive"))
    )
    (net (code "94") (name "unconnected-(H2-Pad6)") (class "Default")
      (node (ref "H2") (pin "6") (pinfunction "6_6") (pintype "passive"))
    )
    (net (code "95") (name "unconnected-(H2-Pad7)") (class "Default")
      (node (ref "H2") (pin "7") (pinfunction "7_7") (pintype "passive"))
    )
    (net (code "96") (name "unconnected-(H2-Pad8)") (class "Default")
      (node (ref "H2") (pin "8") (pinfunction "8_8") (pintype "passive"))
    )
    (net (code "97") (name "unconnected-(H2-Pad9)") (class "Default")
      (node (ref "H2") (pin "9") (pinfunction "9_9") (pintype "passive"))
    )
    (net (code "98") (name "unconnected-(H2-Pad10)") (class "Default")
      (node (ref "H2") (pin "10") (pinfunction "10_10") (pintype "passive"))
    )
    (net (code "99") (name "unconnected-(H2-Pad11)") (class "Default")
      (node (ref "H2") (pin "11") (pinfunction "11_11") (pintype "passive"))
    )
    (net (code "100") (name "unconnected-(H2-Pad12)") (class "Default")
      (node (ref "H2") (pin "12") (pinfunction "12_12") (pintype "passive"))
    )
    (net (code "101") (name "unconnected-(H2-Pad13)") (class "Default")
      (node (ref "H2") (pin "13") (pinfunction "13_13") (pintype "passive"))
    )
    (net (code "102") (name "unconnected-(H2-Pad14)") (class "Default")
      (node (ref "H2") (pin "14") (pinfunction "14_14") (pintype "passive"))
    )
    (net (code "103") (name "unconnected-(H2-Pad15)") (class "Default")
      (node (ref "H2") (pin "15") (pinfunction "15_15") (pintype "passive"))
    )
    (net (code "104") (name "unconnected-(H2-Pad16)") (class "Default")
      (node (ref "H2") (pin "16") (pinfunction "16_16") (pintype "passive"))
    )
    (net (code "105") (name "unconnected-(H2-Pad17)") (class "Default")
      (node (ref "H2") (pin "17") (pinfunction "17_17") (pintype "passive"))
    )
    (net (code "106") (name "unconnected-(H2-Pad18)") (class "Default")
      (node (ref "H2") (pin "18") (pinfunction "18_18") (pintype "passive"))
    )
    (net (code "107") (name "unconnected-(H2-Pad19)") (class "Default")
      (node (ref "H2") (pin "19") (pinfunction "19_19") (pintype "passive"))
    )
    (net (code "108") (name "unconnected-(H2-Pad20)") (class "Default")
      (node (ref "H2") (pin "20") (pinfunction "20_20") (pintype "passive"))
    )
    (net (code "109") (name "unconnected-(H2-Pad21)") (class "Default")
      (node (ref "H2") (pin "21") (pinfunction "21_21") (pintype "passive"))
    )
    (net (code "110") (name "unconnected-(H2-Pad22)") (class "Default")
      (node (ref "H2") (pin "22") (pinfunction "22_22") (pintype "passive"))
    )
    (net (code "111") (name "unconnected-(H2-Pad23)") (class "Default")
      (node (ref "H2") (pin "23") (pinfunction "23_23") (pintype "passive"))
    )
    (net (code "112") (name "unconnected-(H2-Pad24)") (class "Default")
      (node (ref "H2") (pin "24") (pinfunction "24_24") (pintype "passive"))
    )
    (net (code "113") (name "unconnected-(H2-Pad33)") (class "Default")
      (node (ref "H2") (pin "33") (pinfunction "33_33") (pintype "passive"))
    )
    (net (code "114") (name "unconnected-(H2-Pad34)") (class "Default")
      (node (ref "H2") (pin "34") (pinfunction "34_34") (pintype "passive"))
    )
    (net (code "115") (name "unconnected-(H2-Pad35)") (class "Default")
      (node (ref "H2") (pin "35") (pinfunction "35_35") (pintype "passive"))
    )
    (net (code "116") (name "unconnected-(H2-Pad36)") (class "Default")
      (node (ref "H2") (pin "36") (pinfunction "36_36") (pintype "passive"))
    )
    (net (code "117") (name "unconnected-(H2-Pad37)") (class "Default")
      (node (ref "H2") (pin "37") (pinfunction "37_37") (pintype "passive"))
    )
    (net (code "118") (name "unconnected-(H2-Pad38)") (class "Default")
      (node (ref "H2") (pin "38") (pinfunction "38_38") (pintype "passive"))
    )
    (net (code "119") (name "unconnected-(H2-Pad39)") (class "Default")
      (node (ref "H2") (pin "39") (pinfunction "39_39") (pintype "passive"))
    )
    (net (code "120") (name "unconnected-(H2-Pad40)") (class "Default")
      (node (ref "H2") (pin "40") (pinfunction "40_40") (pintype "passive"))
    )
    (net (code "121") (name "unconnected-(H2-Pad41)") (class "Default")
      (node (ref "H2") (pin "41") (pinfunction "41_41") (pintype "passive"))
    )
    (net (code "122") (name "unconnected-(H2-Pad42)") (class "Default")
      (node (ref "H2") (pin "42") (pinfunction "42_42") (pintype "passive"))
    )
    (net (code "123") (name "unconnected-(H2-Pad43)") (class "Default")
      (node (ref "H2") (pin "43") (pinfunction "43_43") (pintype "passive"))
    )
    (net (code "124") (name "unconnected-(H2-Pad44)") (class "Default")
      (node (ref "H2") (pin "44") (pinfunction "44_44") (pintype "passive"))
    )
    (net (code "125") (name "unconnected-(H2-Pad47)") (class "Default")
      (node (ref "H2") (pin "47") (pinfunction "47_47") (pintype "passive"))
    )
    (net (code "126") (name "unconnected-(H2-Pad48)") (class "Default")
      (node (ref "H2") (pin "48") (pinfunction "48_48") (pintype "passive"))
    )
    (net (code "127") (name "unconnected-(H2-Pad49)") (class "Default")
      (node (ref "H2") (pin "49") (pinfunction "49_49") (pintype "passive"))
    )
    (net (code "128") (name "unconnected-(H2-Pad50)") (class "Default")
      (node (ref "H2") (pin "50") (pinfunction "50_50") (pintype "passive"))
    )
    (net (code "129") (name "unconnected-(H2-Pad51)") (class "Default")
      (node (ref "H2") (pin "51") (pinfunction "51_51") (pintype "passive"))
    )
    (net (code "130") (name "unconnected-(H2-Pad52)") (class "Default")
      (node (ref "H2") (pin "52") (pinfunction "52_52") (pintype "passive"))
    )
    (net (code "131") (name "unconnected-(U$2-PadP2)") (class "Default")
      (node (ref "U$2") (pin "P2") (pinfunction "P2_P2") (pintype "bidirectional"))
    )
    (net (code "132") (name "unconnected-(U$2-PadP5)") (class "Default")
      (node (ref "U$2") (pin "P5") (pinfunction "P5_P5") (pintype "bidirectional"))
    )
    (net (code "133") (name "unconnected-(U$3-PadP2)") (class "Default")
      (node (ref "U$3") (pin "P2") (pinfunction "P2_P2") (pintype "bidirectional"))
    )
    (net (code "134") (name "unconnected-(U$3-PadP5)") (class "Default")
      (node (ref "U$3") (pin "P5") (pinfunction "P5_P5") (pintype "bidirectional"))
    )
    (net (code "135") (name "unconnected-(U$4-PadP2)") (class "Default")
      (node (ref "U$4") (pin "P2") (pinfunction "P2_P2") (pintype "bidirectional"))
    )
    (net (code "136") (name "unconnected-(U$4-PadP5)") (class "Default")
      (node (ref "U$4") (pin "P5") (pinfunction "P5_P5") (pintype "bidirectional"))
    )
    (net (code "137") (name "unconnected-(U$5-PadP2)") (class "Default")
      (node (ref "U$5") (pin "P2") (pinfunction "P2_P2") (pintype "bidirectional"))
    )
    (net (code "138") (name "unconnected-(U$5-PadP5)") (class "Default")
      (node (ref "U$5") (pin "P5") (pinfunction "P5_P5") (pintype "bidirectional"))
    )
    (net (code "139") (name "unconnected-(U$13-PadCONFIG)") (class "Default")
      (node (ref "U$13") (pin "CONFIG") (pinfunction "CONFIG_CONFIG") (pintype "bidirectional"))
    )
    (net (code "140") (name "unconnected-(U$13-PadCWDT)") (class "Default")
      (node (ref "U$13") (pin "CWDT") (pinfunction "CWDT_CWDT") (pintype "bidirectional"))
    )
    (net (code "141") (name "unconnected-(U$13-PadWDI)") (class "Default")
      (node (ref "U$13") (pin "WDI") (pinfunction "WDI_WDI") (pintype "bidirectional"))
    )
    (net (code "142") (name "unconnected-(U$13-~{RST1}-PadRST1)") (class "Default")
      (node (ref "U$13") (pin "RST1") (pinfunction "~{RST1}_RST1") (pintype "bidirectional"))
    )
    (net (code "143") (name "unconnected-(U$13-~{RST2}-PadRST2)") (class "Default")
      (node (ref "U$13") (pin "RST2") (pinfunction "~{RST2}_RST2") (pintype "bidirectional"))
    )
    (net (code "144") (name "unconnected-(U$13-~{WDO}-PadWDO)") (class "Default")
      (node (ref "U$13") (pin "WDO") (pinfunction "~{WDO}_WDO") (pintype "bidirectional"))
    )
  )
)
